# carcomputer_split3_bottom.net
KiCad netlist of a schematic drawn in EAGLE
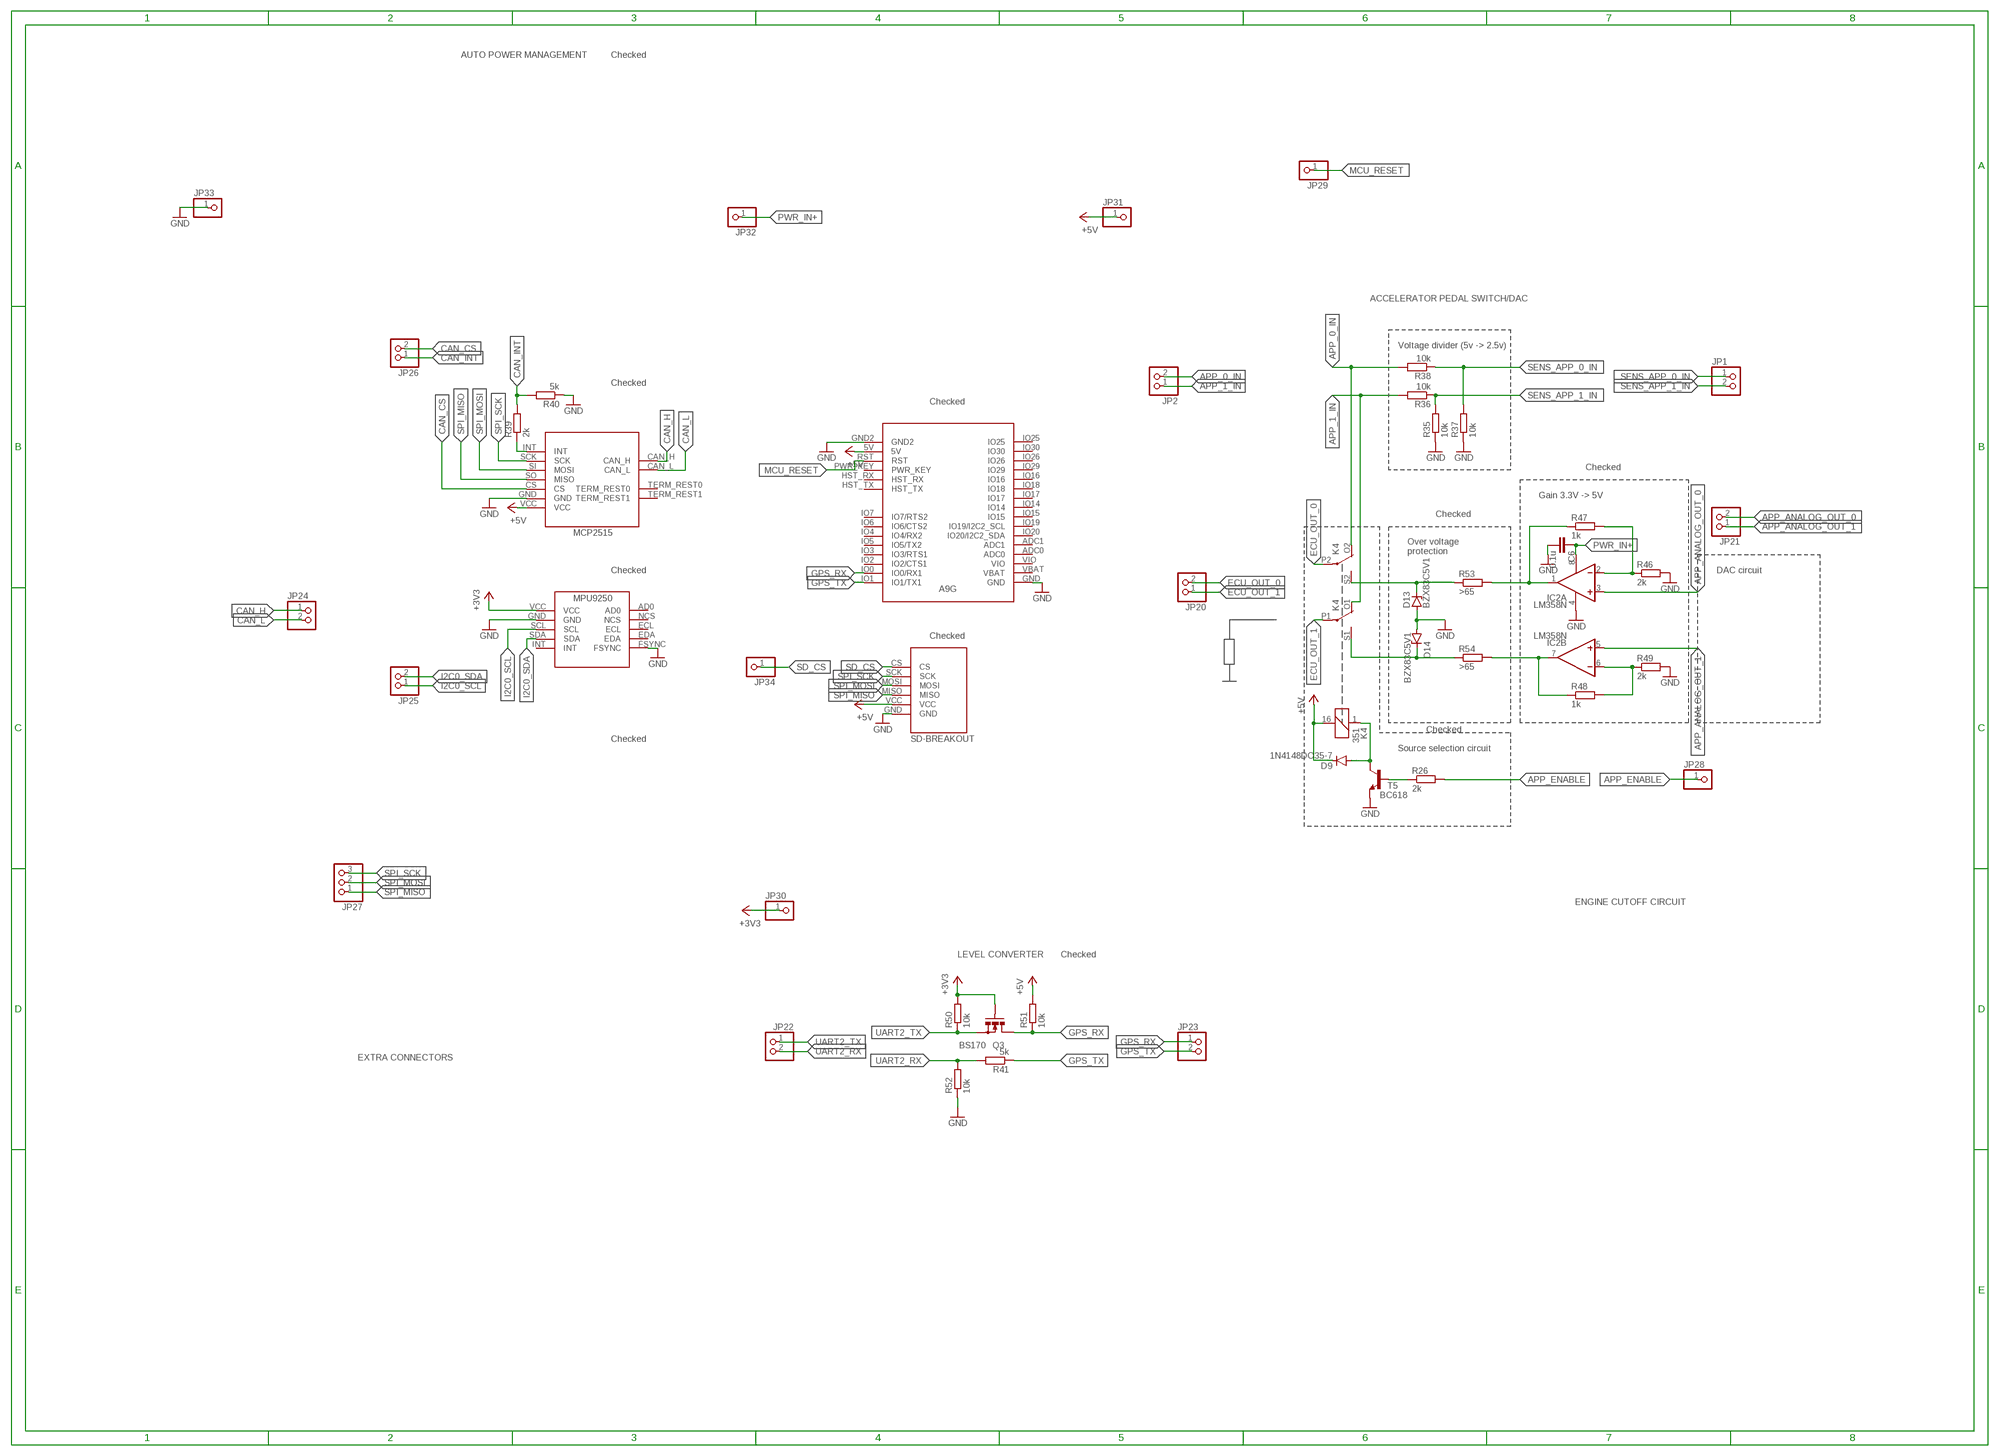
[diagram p0: schematic, sheet 1]

(export (version "E")
  (design (tool "Eeschema 10.0.6"))
  (components
    (comp (ref "C6")
      (value "0.1u")
      (footprint "eagle-import:C025-050X050")
      (libsource (lib "eagle-import") (part "C-EU025-050X050"))
    )
    (comp (ref "D9")
      (value "1N4148DO35-7")
      (footprint "eagle-import:DO35-7")
      (libsource (lib "eagle-import") (part "1N4148DO35-7"))
    )
    (comp (ref "D13")
      (value "BZX83C5V1")
      (footprint "eagle-import:DO41Z10")
      (libsource (lib "eagle-import") (part "BZX85"))
    )
    (comp (ref "D14")
      (value "BZX83C5V1")
      (footprint "eagle-import:DO41Z10")
      (libsource (lib "eagle-import") (part "BZX85"))
    )
    (comp (ref "IC2")
      (value "LM358N")
      (footprint "eagle-import:DIL08")
      (libsource (lib "eagle-import") (part "LM358N"))
    )
    (comp (ref "JP1")
      (value "PINHD-1X2")
      (footprint "eagle-import:1X02")
      (libsource (lib "eagle-import") (part "PINHD-1X2"))
    )
    (comp (ref "JP2")
      (value "PINHD-1X2")
      (footprint "eagle-import:1X02")
      (libsource (lib "eagle-import") (part "PINHD-1X2"))
    )
    (comp (ref "JP20")
      (value "PINHD-1X2")
      (footprint "eagle-import:1X02")
      (libsource (lib "eagle-import") (part "PINHD-1X2"))
    )
    (comp (ref "JP21")
      (value "PINHD-1X2")
      (footprint "eagle-import:1X02")
      (libsource (lib "eagle-import") (part "PINHD-1X2"))
    )
    (comp (ref "JP22")
      (value "PINHD-1X2")
      (footprint "eagle-import:1X02")
      (libsource (lib "eagle-import") (part "PINHD-1X2"))
    )
    (comp (ref "JP23")
      (value "PINHD-1X2")
      (footprint "eagle-import:1X02")
      (libsource (lib "eagle-import") (part "PINHD-1X2"))
    )
    (comp (ref "JP24")
      (value "PINHD-1X2")
      (footprint "eagle-import:1X02")
      (libsource (lib "eagle-import") (part "PINHD-1X2"))
    )
    (comp (ref "JP25")
      (value "PINHD-1X2")
      (footprint "eagle-import:1X02")
      (libsource (lib "eagle-import") (part "PINHD-1X2"))
    )
    (comp (ref "JP26")
      (value "PINHD-1X2")
      (footprint "eagle-import:1X02")
      (libsource (lib "eagle-import") (part "PINHD-1X2"))
    )
    (comp (ref "JP27")
      (value "PINHD-1X3")
      (footprint "eagle-import:1X03")
      (libsource (lib "eagle-import") (part "PINHD-1X3"))
    )
    (comp (ref "JP28")
      (value "PINHD-1X1")
      (footprint "eagle-import:1X01")
      (libsource (lib "eagle-import") (part "PINHD-1X1"))
    )
    (comp (ref "JP29")
      (value "PINHD-1X1")
      (footprint "eagle-import:1X01")
      (libsource (lib "eagle-import") (part "PINHD-1X1"))
    )
    (comp (ref "JP30")
      (value "PINHD-1X1")
      (footprint "eagle-import:1X01")
      (libsource (lib "eagle-import") (part "PINHD-1X1"))
    )
    (comp (ref "JP31")
      (value "PINHD-1X1")
      (footprint "eagle-import:1X01")
      (libsource (lib "eagle-import") (part "PINHD-1X1"))
    )
    (comp (ref "JP32")
      (value "PINHD-1X1")
      (footprint "eagle-import:1X01")
      (libsource (lib "eagle-import") (part "PINHD-1X1"))
    )
    (comp (ref "JP33")
      (value "PINHD-1X1")
      (footprint "eagle-import:1X01")
      (libsource (lib "eagle-import") (part "PINHD-1X1"))
    )
    (comp (ref "JP34")
      (value "PINHD-1X1")
      (footprint "eagle-import:1X01")
      (libsource (lib "eagle-import") (part "PINHD-1X1"))
    )
    (comp (ref "K4")
      (value "351")
      (footprint "eagle-import:351")
      (libsource (lib "eagle-import") (part "351"))
    )
    (comp (ref "Q3")
      (value "BS170")
      (footprint "eagle-import:SOT54E")
      (libsource (lib "eagle-import") (part "BS170"))
    )
    (comp (ref "R26")
      (value "2k")
      (footprint "eagle-import:0207_7")
      (libsource (lib "eagle-import") (part "R-EU_0207/7"))
    )
    (comp (ref "R35")
      (value "10k")
      (footprint "eagle-import:0207_7")
      (libsource (lib "eagle-import") (part "R-EU_0207/7"))
    )
    (comp (ref "R36")
      (value "10k")
      (footprint "eagle-import:0207_7")
      (libsource (lib "eagle-import") (part "R-EU_0207/7"))
    )
    (comp (ref "R37")
      (value "10k")
      (footprint "eagle-import:0207_7")
      (libsource (lib "eagle-import") (part "R-EU_0207/7"))
    )
    (comp (ref "R38")
      (value "10k")
      (footprint "eagle-import:0207_7")
      (libsource (lib "eagle-import") (part "R-EU_0207/7"))
    )
    (comp (ref "R39")
      (value "2k")
      (footprint "eagle-import:0207_7")
      (libsource (lib "eagle-import") (part "R-EU_0207/7"))
    )
    (comp (ref "R40")
      (value "5k")
      (footprint "eagle-import:0207_7")
      (libsource (lib "eagle-import") (part "R-EU_0207/7"))
    )
    (comp (ref "R41")
      (value "5k")
      (footprint "eagle-import:0207_7")
      (libsource (lib "eagle-import") (part "R-EU_0207/7"))
    )
    (comp (ref "R46")
      (value "2k")
      (footprint "eagle-import:0207_7")
      (libsource (lib "eagle-import") (part "R-EU_0207/7"))
    )
    (comp (ref "R47")
      (value "1k")
      (footprint "eagle-import:0207_7")
      (libsource (lib "eagle-import") (part "R-EU_0207/7"))
    )
    (comp (ref "R48")
      (value "1k")
      (footprint "eagle-import:0207_7")
      (libsource (lib "eagle-import") (part "R-EU_0207/7"))
    )
    (comp (ref "R49")
      (value "2k")
      (footprint "eagle-import:0207_7")
      (libsource (lib "eagle-import") (part "R-EU_0207/7"))
    )
    (comp (ref "R50")
      (value "10k")
      (footprint "eagle-import:0207_7")
      (libsource (lib "eagle-import") (part "R-EU_0207/7"))
    )
    (comp (ref "R51")
      (value "10k")
      (footprint "eagle-import:0207_7")
      (libsource (lib "eagle-import") (part "R-EU_0207/7"))
    )
    (comp (ref "R52")
      (value "10k")
      (footprint "eagle-import:0207_7")
      (libsource (lib "eagle-import") (part "R-EU_0207/7"))
    )
    (comp (ref "R53")
      (value ">65")
      (footprint "eagle-import:0207_7")
      (libsource (lib "eagle-import") (part "R-EU_0207/7"))
    )
    (comp (ref "R54")
      (value ">65")
      (footprint "eagle-import:0207_7")
      (libsource (lib "eagle-import") (part "R-EU_0207/7"))
    )
    (comp (ref "T5")
      (value "BC618")
      (footprint "eagle-import:TO92-EBC")
      (libsource (lib "eagle-import") (part "BC618"))
    )
    (comp (ref "U$8")
      (value "MCP2515_DEVBOARDINVERTED")
      (footprint "eagle-import:MCP2515_DEVBOARD_INVERTED")
      (libsource (lib "eagle-import") (part "MCP2515_DEVBOARDINVERTED"))
    )
    (comp (ref "U$9")
      (value "MPU9250_BREAKOUT")
      (footprint "eagle-import:MPU9250_BREAKOUT")
      (libsource (lib "eagle-import") (part "MPU9250_BREAKOUT"))
    )
    (comp (ref "U$11")
      (value "HKD-MICRO-SD-BREAKOUT")
      (footprint "eagle-import:HKD-MICRO-SD-BREAKOUT")
      (libsource (lib "eagle-import") (part "HKD-MICRO-SD-BREAKOUT"))
    )
    (comp (ref "U$12")
      (value "A9G")
      (footprint "eagle-import:A9G")
      (libsource (lib "eagle-import") (part "A9G"))
    )
  )
  (nets
    (net (code "1") (name "+3V3") (class "Default")
      (node (ref "JP30") (pin "1") (pinfunction "1_1") (pintype "passive"))
      (node (ref "Q3") (pin "G") (pinfunction "G_G") (pintype "passive"))
      (node (ref "R50") (pin "2") (pinfunction "2_2") (pintype "passive"))
      (node (ref "U$9") (pin "VCC") (pinfunction "VCC_VCC") (pintype "bidirectional"))
    )
    (net (code "2") (name "+5V") (class "Default")
      (node (ref "D9") (pin "C") (pinfunction "C_C") (pintype "passive"))
      (node (ref "JP31") (pin "1") (pinfunction "1_1") (pintype "passive"))
      (node (ref "K4") (pin "16") (pinfunction "2_16") (pintype "passive"))
      (node (ref "R51") (pin "2") (pinfunction "2_2") (pintype "passive"))
      (node (ref "U$11") (pin "VCC") (pinfunction "VCC_VCC") (pintype "bidirectional"))
      (node (ref "U$12") (pin "5V") (pinfunction "5V_5V") (pintype "bidirectional"))
      (node (ref "U$8") (pin "VCC") (pinfunction "VCC_VCC") (pintype "bidirectional"))
    )
    (net (code "3") (name "APP_0_IN") (class "Default")
      (node (ref "JP2") (pin "2") (pinfunction "2_2") (pintype "passive"))
      (node (ref "K4") (pin "O2") (pinfunction "O_O2") (pintype "passive"))
      (node (ref "R38") (pin "2") (pinfunction "2_2") (pintype "passive"))
    )
    (net (code "4") (name "APP_1_IN") (class "Default")
      (node (ref "JP2") (pin "1") (pinfunction "1_1") (pintype "passive"))
      (node (ref "K4") (pin "O1") (pinfunction "O_O1") (pintype "passive"))
      (node (ref "R36") (pin "2") (pinfunction "2_2") (pintype "passive"))
    )
    (net (code "5") (name "APP_ANALOG_OUT_0") (class "Default")
      (node (ref "IC2") (pin "3") (pinfunction "+IN_3") (pintype "input"))
      (node (ref "JP21") (pin "2") (pinfunction "2_2") (pintype "passive"))
    )
    (net (code "6") (name "APP_ANALOG_OUT_1") (class "Default")
      (node (ref "IC2") (pin "5") (pinfunction "+IN_5") (pintype "input"))
      (node (ref "JP21") (pin "1") (pinfunction "1_1") (pintype "passive"))
    )
    (net (code "7") (name "APP_ENABLE") (class "Default")
      (node (ref "JP28") (pin "1") (pinfunction "1_1") (pintype "passive"))
      (node (ref "R26") (pin "2") (pinfunction "2_2") (pintype "passive"))
    )
    (net (code "8") (name "CAN_CS") (class "Default")
      (node (ref "JP26") (pin "2") (pinfunction "2_2") (pintype "passive"))
      (node (ref "U$8") (pin "CS") (pinfunction "CS_CS") (pintype "input"))
    )
    (net (code "9") (name "CAN_H") (class "Default")
      (node (ref "JP24") (pin "1") (pinfunction "1_1") (pintype "passive"))
      (node (ref "U$8") (pin "CAN_H") (pinfunction "CAN_H_CAN_H") (pintype "bidirectional"))
    )
    (net (code "10") (name "CAN_INT") (class "Default")
      (node (ref "JP26") (pin "1") (pinfunction "1_1") (pintype "passive"))
      (node (ref "R39") (pin "2") (pinfunction "2_2") (pintype "passive"))
      (node (ref "R40") (pin "2") (pinfunction "2_2") (pintype "passive"))
    )
    (net (code "11") (name "CAN_L") (class "Default")
      (node (ref "JP24") (pin "2") (pinfunction "2_2") (pintype "passive"))
      (node (ref "U$8") (pin "CAN_L") (pinfunction "CAN_L_CAN_L") (pintype "bidirectional"))
    )
    (net (code "12") (name "ECU_OUT_0") (class "Default")
      (node (ref "JP20") (pin "2") (pinfunction "2_2") (pintype "passive"))
      (node (ref "K4") (pin "P2") (pinfunction "P_P2") (pintype "passive"))
    )
    (net (code "13") (name "ECU_OUT_1") (class "Default")
      (node (ref "JP20") (pin "1") (pinfunction "1_1") (pintype "passive"))
      (node (ref "K4") (pin "P1") (pinfunction "P_P1") (pintype "passive"))
    )
    (net (code "14") (name "GND") (class "Default")
      (node (ref "C6") (pin "2") (pinfunction "2_2") (pintype "passive"))
      (node (ref "D13") (pin "A") (pinfunction "A_A") (pintype "passive"))
      (node (ref "D14") (pin "A") (pinfunction "A_A") (pintype "passive"))
      (node (ref "IC2") (pin "4") (pinfunction "V-_4") (pintype "power_in"))
      (node (ref "JP33") (pin "1") (pinfunction "1_1") (pintype "passive"))
      (node (ref "R35") (pin "1") (pinfunction "1_1") (pintype "passive"))
      (node (ref "R37") (pin "1") (pinfunction "1_1") (pintype "passive"))
      (node (ref "R40") (pin "1") (pinfunction "1_1") (pintype "passive"))
      (node (ref "R46") (pin "2") (pinfunction "2_2") (pintype "passive"))
      (node (ref "R49") (pin "2") (pinfunction "2_2") (pintype "passive"))
      (node (ref "R52") (pin "1") (pinfunction "1_1") (pintype "passive"))
      (node (ref "T5") (pin "E") (pinfunction "E_E") (pintype "passive"))
      (node (ref "U$11") (pin "GND") (pinfunction "GND_GND") (pintype "bidirectional"))
      (node (ref "U$12") (pin "GND") (pinfunction "GND_GND") (pintype "bidirectional"))
      (node (ref "U$12") (pin "GND2") (pinfunction "GND2_GND2") (pintype "bidirectional"))
      (node (ref "U$8") (pin "GND") (pinfunction "GND_GND") (pintype "bidirectional"))
      (node (ref "U$9") (pin "FSYNC") (pinfunction "FSYNC_FSYNC") (pintype "bidirectional"))
      (node (ref "U$9") (pin "GND") (pinfunction "GND_GND") (pintype "bidirectional"))
    )
    (net (code "15") (name "GPS_RX") (class "Default")
      (node (ref "JP23") (pin "1") (pinfunction "1_1") (pintype "passive"))
      (node (ref "Q3") (pin "D") (pinfunction "D_D") (pintype "passive"))
      (node (ref "R51") (pin "1") (pinfunction "1_1") (pintype "passive"))
      (node (ref "U$12") (pin "IO0") (pinfunction "IO0/RX1_IO0") (pintype "bidirectional"))
    )
    (net (code "16") (name "GPS_TX") (class "Default")
      (node (ref "JP23") (pin "2") (pinfunction "2_2") (pintype "passive"))
      (node (ref "R41") (pin "1") (pinfunction "1_1") (pintype "passive"))
      (node (ref "U$12") (pin "IO1") (pinfunction "IO1/TX1_IO1") (pintype "bidirectional"))
    )
    (net (code "17") (name "I2C0_SCL") (class "Default")
      (node (ref "JP25") (pin "1") (pinfunction "1_1") (pintype "passive"))
      (node (ref "U$9") (pin "SCL") (pinfunction "SCL_SCL") (pintype "bidirectional"))
    )
    (net (code "18") (name "I2C0_SDA") (class "Default")
      (node (ref "JP25") (pin "2") (pinfunction "2_2") (pintype "passive"))
      (node (ref "U$9") (pin "SDA") (pinfunction "SDA_SDA") (pintype "bidirectional"))
    )
    (net (code "19") (name "MCU_RESET") (class "Default")
      (node (ref "JP29") (pin "1") (pinfunction "1_1") (pintype "passive"))
      (node (ref "U$12") (pin "RST") (pinfunction "RST_RST") (pintype "bidirectional"))
    )
    (net (code "20") (name "Net-(D9-PadA)") (class "Default")
      (node (ref "D9") (pin "A") (pinfunction "A_A") (pintype "passive"))
      (node (ref "K4") (pin "1") (pinfunction "1_1") (pintype "passive"))
      (node (ref "T5") (pin "C") (pinfunction "C_C") (pintype "passive"))
    )
    (net (code "21") (name "Net-(IC2A--IN)") (class "Default")
      (node (ref "IC2") (pin "2") (pinfunction "-IN_2") (pintype "input"))
      (node (ref "R46") (pin "1") (pinfunction "1_1") (pintype "passive"))
      (node (ref "R47") (pin "2") (pinfunction "2_2") (pintype "passive"))
    )
    (net (code "22") (name "Net-(IC2A-OUT)") (class "Default")
      (node (ref "IC2") (pin "1") (pinfunction "OUT_1") (pintype "output"))
      (node (ref "R47") (pin "1") (pinfunction "1_1") (pintype "passive"))
      (node (ref "R53") (pin "2") (pinfunction "2_2") (pintype "passive"))
    )
    (net (code "23") (name "Net-(IC2B--IN)") (class "Default")
      (node (ref "IC2") (pin "6") (pinfunction "-IN_6") (pintype "input"))
      (node (ref "R48") (pin "2") (pinfunction "2_2") (pintype "passive"))
      (node (ref "R49") (pin "1") (pinfunction "1_1") (pintype "passive"))
    )
    (net (code "24") (name "Net-(IC2B-OUT)") (class "Default")
      (node (ref "IC2") (pin "7") (pinfunction "OUT_7") (pintype "output"))
      (node (ref "R48") (pin "1") (pinfunction "1_1") (pintype "passive"))
      (node (ref "R54") (pin "2") (pinfunction "2_2") (pintype "passive"))
    )
    (net (code "25") (name "Net-(K4B-S)") (class "Default")
      (node (ref "D14") (pin "C") (pinfunction "C_C") (pintype "passive"))
      (node (ref "K4") (pin "S1") (pinfunction "S_S1") (pintype "passive"))
      (node (ref "R54") (pin "1") (pinfunction "1_1") (pintype "passive"))
    )
    (net (code "26") (name "Net-(K4C-S)") (class "Default")
      (node (ref "D13") (pin "C") (pinfunction "C_C") (pintype "passive"))
      (node (ref "K4") (pin "S2") (pinfunction "S_S2") (pintype "passive"))
      (node (ref "R53") (pin "1") (pinfunction "1_1") (pintype "passive"))
    )
    (net (code "27") (name "Net-(R26-Pad1)") (class "Default")
      (node (ref "R26") (pin "1") (pinfunction "1_1") (pintype "passive"))
      (node (ref "T5") (pin "B") (pinfunction "B_B") (pintype "passive"))
    )
    (net (code "28") (name "Net-(R39-Pad1)") (class "Default")
      (node (ref "R39") (pin "1") (pinfunction "1_1") (pintype "passive"))
      (node (ref "U$8") (pin "INT") (pinfunction "INT_INT") (pintype "output"))
    )
    (net (code "29") (name "PWR_IN+") (class "Default")
      (node (ref "C6") (pin "1") (pinfunction "1_1") (pintype "passive"))
      (node (ref "IC2") (pin "8") (pinfunction "V+_8") (pintype "power_in"))
      (node (ref "JP32") (pin "1") (pinfunction "1_1") (pintype "passive"))
    )
    (net (code "30") (name "SD_CS") (class "Default")
      (node (ref "JP34") (pin "1") (pinfunction "1_1") (pintype "passive"))
      (node (ref "U$11") (pin "CS") (pinfunction "CS_CS") (pintype "bidirectional"))
    )
    (net (code "31") (name "SENS_APP_0_IN") (class "Default")
      (node (ref "JP1") (pin "1") (pinfunction "1_1") (pintype "passive"))
      (node (ref "R37") (pin "2") (pinfunction "2_2") (pintype "passive"))
      (node (ref "R38") (pin "1") (pinfunction "1_1") (pintype "passive"))
    )
    (net (code "32") (name "SENS_APP_1_IN") (class "Default")
      (node (ref "JP1") (pin "2") (pinfunction "2_2") (pintype "passive"))
      (node (ref "R35") (pin "2") (pinfunction "2_2") (pintype "passive"))
      (node (ref "R36") (pin "1") (pinfunction "1_1") (pintype "passive"))
    )
    (net (code "33") (name "SPI_MISO") (class "Default")
      (node (ref "JP27") (pin "1") (pinfunction "1_1") (pintype "passive"))
      (node (ref "U$11") (pin "MISO") (pinfunction "MISO_MISO") (pintype "bidirectional"))
      (node (ref "U$8") (pin "SO") (pinfunction "MISO_SO") (pintype "output"))
    )
    (net (code "34") (name "SPI_MOSI") (class "Default")
      (node (ref "JP27") (pin "2") (pinfunction "2_2") (pintype "passive"))
      (node (ref "U$11") (pin "MOSI") (pinfunction "MOSI_MOSI") (pintype "bidirectional"))
      (node (ref "U$8") (pin "SI") (pinfunction "MOSI_SI") (pintype "input"))
    )
    (net (code "35") (name "SPI_SCK") (class "Default")
      (node (ref "JP27") (pin "3") (pinfunction "3_3") (pintype "passive"))
      (node (ref "U$11") (pin "SCK") (pinfunction "SCK_SCK") (pintype "bidirectional"))
      (node (ref "U$8") (pin "SCK") (pinfunction "SCK_SCK") (pintype "input"))
    )
    (net (code "36") (name "UART2_RX") (class "Default")
      (node (ref "JP22") (pin "2") (pinfunction "2_2") (pintype "passive"))
      (node (ref "R41") (pin "2") (pinfunction "2_2") (pintype "passive"))
      (node (ref "R52") (pin "2") (pinfunction "2_2") (pintype "passive"))
    )
    (net (code "37") (name "UART2_TX") (class "Default")
      (node (ref "JP22") (pin "1") (pinfunction "1_1") (pintype "passive"))
      (node (ref "Q3") (pin "S") (pinfunction "S_S") (pintype "passive"))
      (node (ref "R50") (pin "1") (pinfunction "1_1") (pintype "passive"))
    )
    (net (code "38") (name "unconnected-(U$8-PadTERM_REST0)") (class "Default")
      (node (ref "U$8") (pin "TERM_REST0") (pinfunction "TERM_REST0_TERM_REST0") (pintype "bidirectional"))
    )
    (net (code "39") (name "unconnected-(U$8-PadTERM_REST1)") (class "Default")
      (node (ref "U$8") (pin "TERM_REST1") (pinfunction "TERM_REST1_TERM_REST1") (pintype "bidirectional"))
    )
    (net (code "40") (name "unconnected-(U$9-PadAD0)") (class "Default")
      (node (ref "U$9") (pin "AD0") (pinfunction "AD0_AD0") (pintype "bidirectional"))
    )
    (net (code "41") (name "unconnected-(U$9-PadECL)") (class "Default")
      (node (ref "U$9") (pin "ECL") (pinfunction "ECL_ECL") (pintype "bidirectional"))
    )
    (net (code "42") (name "unconnected-(U$9-PadEDA)") (class "Default")
      (node (ref "U$9") (pin "EDA") (pinfunction "EDA_EDA") (pintype "bidirectional"))
    )
    (net (code "43") (name "unconnected-(U$9-PadINT)") (class "Default")
      (node (ref "U$9") (pin "INT") (pinfunction "INT_INT") (pintype "bidirectional"))
    )
    (net (code "44") (name "unconnected-(U$9-PadNCS)") (class "Default")
      (node (ref "U$9") (pin "NCS") (pinfunction "NCS_NCS") (pintype "bidirectional"))
    )
    (net (code "45") (name "unconnected-(U$12-IO2{slash}CTS1-PadIO2)") (class "Default")
      (node (ref "U$12") (pin "IO2") (pinfunction "IO2/CTS1_IO2") (pintype "bidirectional"))
    )
    (net (code "46") (name "unconnected-(U$12-IO3{slash}RTS1-PadIO3)") (class "Default")
      (node (ref "U$12") (pin "IO3") (pinfunction "IO3/RTS1_IO3") (pintype "bidirectional"))
    )
    (net (code "47") (name "unconnected-(U$12-IO4{slash}RX2-PadIO4)") (class "Default")
      (node (ref "U$12") (pin "IO4") (pinfunction "IO4/RX2_IO4") (pintype "bidirectional"))
    )
    (net (code "48") (name "unconnected-(U$12-IO5{slash}TX2-PadIO5)") (class "Default")
      (node (ref "U$12") (pin "IO5") (pinfunction "IO5/TX2_IO5") (pintype "bidirectional"))
    )
    (net (code "49") (name "unconnected-(U$12-IO6{slash}CTS2-PadIO6)") (class "Default")
      (node (ref "U$12") (pin "IO6") (pinfunction "IO6/CTS2_IO6") (pintype "bidirectional"))
    )
    (net (code "50") (name "unconnected-(U$12-IO7{slash}RTS2-PadIO7)") (class "Default")
      (node (ref "U$12") (pin "IO7") (pinfunction "IO7/RTS2_IO7") (pintype "bidirectional"))
    )
    (net (code "51") (name "unconnected-(U$12-IO19{slash}I2C2_SCL-PadIO19)") (class "Default")
      (node (ref "U$12") (pin "IO19") (pinfunction "IO19/I2C2_SCL_IO19") (pintype "bidirectional"))
    )
    (net (code "52") (name "unconnected-(U$12-IO20{slash}I2C2_SDA-PadIO20)") (class "Default")
      (node (ref "U$12") (pin "IO20") (pinfunction "IO20/I2C2_SDA_IO20") (pintype "bidirectional"))
    )
    (net (code "53") (name "unconnected-(U$12-PadADC0)") (class "Default")
      (node (ref "U$12") (pin "ADC0") (pinfunction "ADC0_ADC0") (pintype "bidirectional"))
    )
    (net (code "54") (name "unconnected-(U$12-PadADC1)") (class "Default")
      (node (ref "U$12") (pin "ADC1") (pinfunction "ADC1_ADC1") (pintype "bidirectional"))
    )
    (net (code "55") (name "unconnected-(U$12-PadHST_RX)") (class "Default")
      (node (ref "U$12") (pin "HST_RX") (pinfunction "HST_RX_HST_RX") (pintype "bidirectional"))
    )
    (net (code "56") (name "unconnected-(U$12-PadHST_TX)") (class "Default")
      (node (ref "U$12") (pin "HST_TX") (pinfunction "HST_TX_HST_TX") (pintype "bidirectional"))
    )
    (net (code "57") (name "unconnected-(U$12-PadIO14)") (class "Default")
      (node (ref "U$12") (pin "IO14") (pinfunction "IO14_IO14") (pintype "bidirectional"))
    )
    (net (code "58") (name "unconnected-(U$12-PadIO15)") (class "Default")
      (node (ref "U$12") (pin "IO15") (pinfunction "IO15_IO15") (pintype "bidirectional"))
    )
    (net (code "59") (name "unconnected-(U$12-PadIO16)") (class "Default")
      (node (ref "U$12") (pin "IO16") (pinfunction "IO16_IO16") (pintype "bidirectional"))
    )
    (net (code "60") (name "unconnected-(U$12-PadIO17)") (class "Default")
      (node (ref "U$12") (pin "IO17") (pinfunction "IO17_IO17") (pintype "bidirectional"))
    )
    (net (code "61") (name "unconnected-(U$12-PadIO18)") (class "Default")
      (node (ref "U$12") (pin "IO18") (pinfunction "IO18_IO18") (pintype "bidirectional"))
    )
    (net (code "62") (name "unconnected-(U$12-PadIO25)") (class "Default")
      (node (ref "U$12") (pin "IO25") (pinfunction "IO25_IO25") (pintype "bidirectional"))
    )
    (net (code "63") (name "unconnected-(U$12-PadIO26)") (class "Default")
      (node (ref "U$12") (pin "IO26") (pinfunction "IO26_IO26") (pintype "bidirectional"))
    )
    (net (code "64") (name "unconnected-(U$12-PadIO29)") (class "Default")
      (node (ref "U$12") (pin "IO29") (pinfunction "IO29_IO29") (pintype "bidirectional"))
    )
    (net (code "65") (name "unconnected-(U$12-PadIO30)") (class "Default")
      (node (ref "U$12") (pin "IO30") (pinfunction "IO30_IO30") (pintype "bidirectional"))
    )
    (net (code "66") (name "unconnected-(U$12-PadPWR_KEY)") (class "Default")
      (node (ref "U$12") (pin "PWR_KEY") (pinfunction "PWR_KEY_PWR_KEY") (pintype "bidirectional"))
    )
    (net (code "67") (name "unconnected-(U$12-PadVBAT)") (class "Default")
      (node (ref "U$12") (pin "VBAT") (pinfunction "VBAT_VBAT") (pintype "bidirectional"))
    )
    (net (code "68") (name "unconnected-(U$12-PadVIO)") (class "Default")
      (node (ref "U$12") (pin "VIO") (pinfunction "VIO_VIO") (pintype "bidirectional"))
    )
  )
)
